# Smart_Camera_Powersupply_Rev1_0.net
KiCad netlist of a schematic drawn in EAGLE
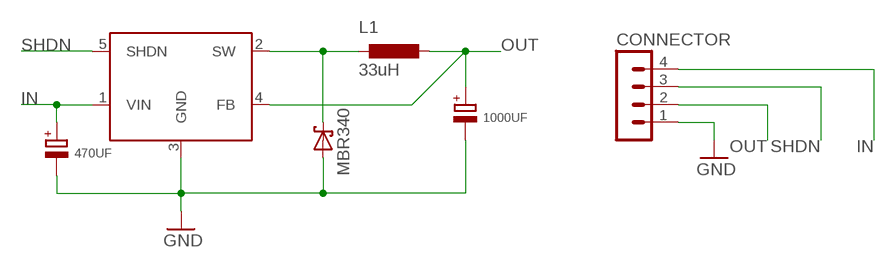
[diagram p0: schematic, sheet 1]

(export (version "E")
  (design (tool "Eeschema 10.0.6"))
  (components
    (comp (ref "C1")
      (value "1000UF")
      (footprint "eagle-import:1000UF")
      (libsource (lib "eagle-import") (part "1000UF"))
    )
    (comp (ref "C2")
      (value "470UF")
      (footprint "eagle-import:470UF")
      (libsource (lib "eagle-import") (part "470UF"))
    )
    (comp (ref "CONNECTOR")
      (value "MA04-1")
      (footprint "eagle-import:MA04-1")
      (libsource (lib "eagle-import") (part "MA04-1"))
    )
    (comp (ref "L1")
      (value "33uH")
      (footprint "eagle-import:L_33UH")
      (libsource (lib "eagle-import") (part "L_33UH"))
    )
    (comp (ref "U$1")
      (value "MBR340")
      (footprint "eagle-import:MBR340")
      (libsource (lib "eagle-import") (part "MBR340"))
    )
    (comp (ref "U$2")
      (value "MIC4576")
      (footprint "eagle-import:MIC4576")
      (libsource (lib "eagle-import") (part "MIC4576"))
    )
  )
  (nets
    (net (code "1") (name "/IN") (class "Default")
      (node (ref "C2") (pin "P$1") (pinfunction "P$1_P$1") (pintype "input"))
      (node (ref "CONNECTOR") (pin "4") (pinfunction "4_4") (pintype "passive"))
      (node (ref "U$2") (pin "1") (pinfunction "VIN_1") (pintype "bidirectional"))
    )
    (net (code "2") (name "/OUT") (class "Default")
      (node (ref "C1") (pin "P$1") (pinfunction "P$1_P$1") (pintype "input"))
      (node (ref "CONNECTOR") (pin "2") (pinfunction "2_2") (pintype "passive"))
      (node (ref "L1") (pin "P$1") (pinfunction "P$1_P$1") (pintype "bidirectional"))
      (node (ref "U$2") (pin "4") (pinfunction "FB_4") (pintype "bidirectional"))
    )
    (net (code "3") (name "/SHDN") (class "Default")
      (node (ref "CONNECTOR") (pin "3") (pinfunction "3_3") (pintype "passive"))
      (node (ref "U$2") (pin "5") (pinfunction "SHDN_5") (pintype "bidirectional"))
    )
    (net (code "4") (name "GND") (class "Default")
      (node (ref "C1") (pin "P$2") (pinfunction "P$2_P$2") (pintype "bidirectional"))
      (node (ref "C2") (pin "P$2") (pinfunction "P$2_P$2") (pintype "bidirectional"))
      (node (ref "CONNECTOR") (pin "1") (pinfunction "1_1") (pintype "passive"))
      (node (ref "U$1") (pin "P$2") (pinfunction "C_P$2") (pintype "passive"))
      (node (ref "U$2") (pin "3") (pinfunction "GND_3") (pintype "bidirectional"))
    )
    (net (code "5") (name "Net-(U$1-A)") (class "Default")
      (node (ref "L1") (pin "P$2") (pinfunction "P$2_P$2") (pintype "bidirectional"))
      (node (ref "U$1") (pin "P$1") (pinfunction "A_P$1") (pintype "passive"))
      (node (ref "U$2") (pin "2") (pinfunction "SW_2") (pintype "bidirectional"))
    )
  )
)
